# ddr3.net
KiCad netlist of a schematic drawn in Altium Designer
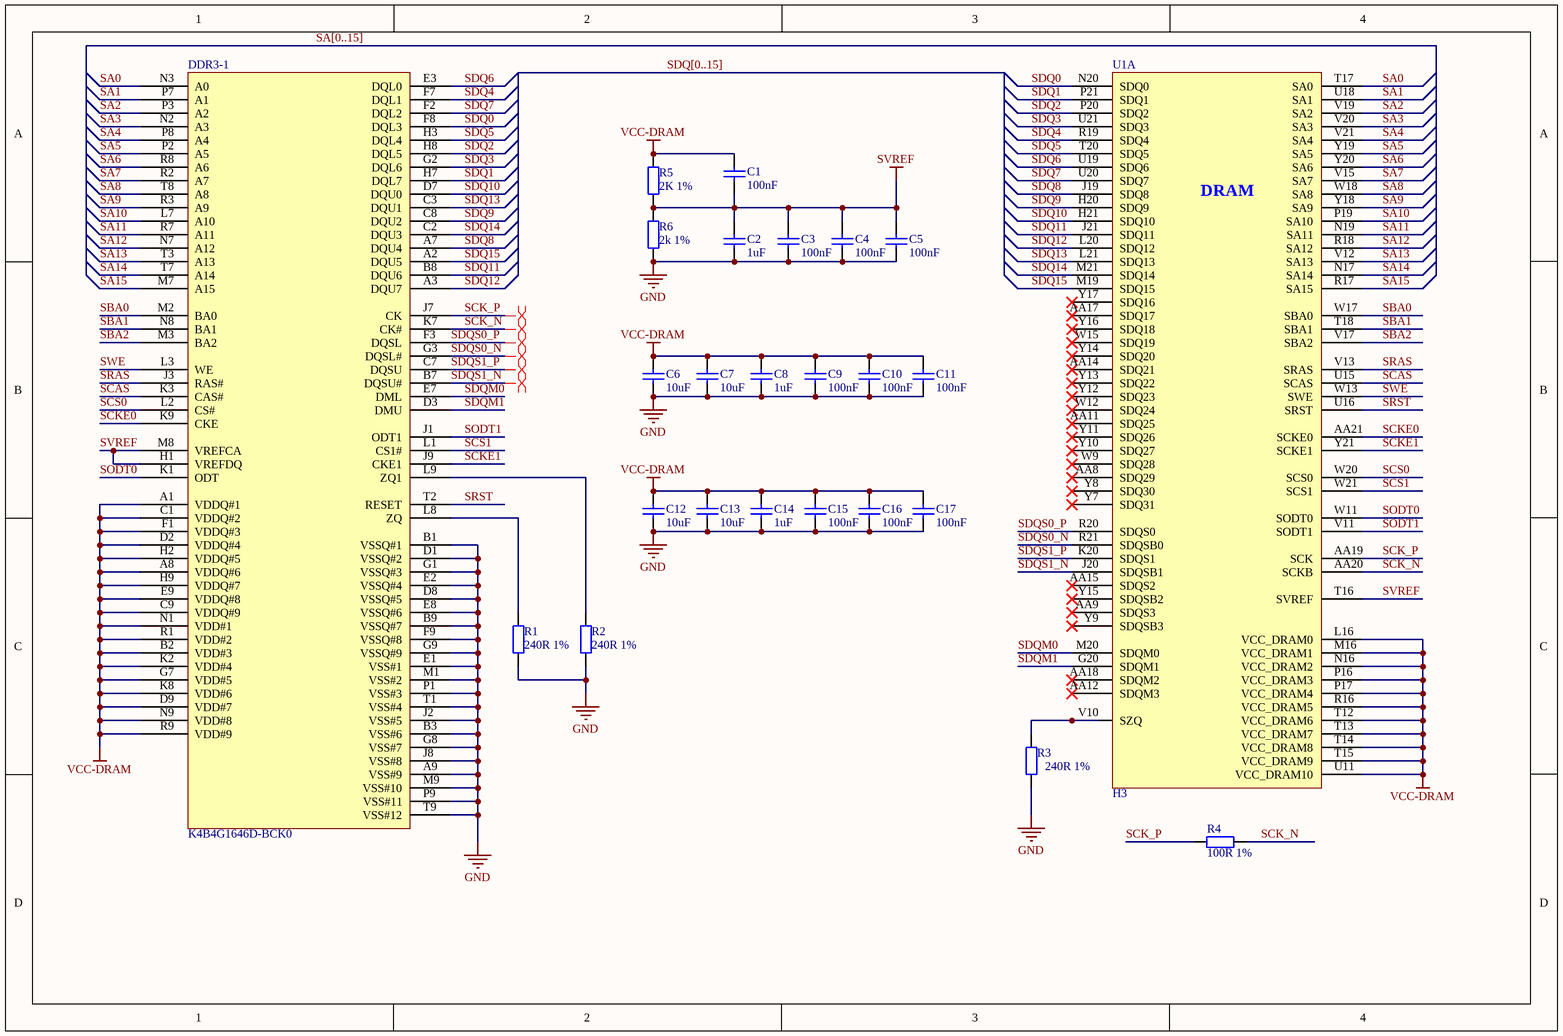
[diagram p0: ddr3.SchDoc]

(export (version "E")
  (design (tool "Eeschema 10.0.6"))
  (components
    (comp (ref "C1")
      (value "100nF")
      (footprint "0402_C")
      (description "smd capacitor")
      (libsource (lib "Schlib") (part "CAP-SMD"))
    )
    (comp (ref "C2")
      (value "1uF")
      (footprint "0402_C")
      (description "smd capacitor")
      (libsource (lib "Schlib") (part "CAP-SMD"))
    )
    (comp (ref "C3")
      (value "100nF")
      (footprint "0402_C")
      (description "smd capacitor")
      (libsource (lib "Schlib") (part "CAP-SMD"))
    )
    (comp (ref "C4")
      (value "100nF")
      (footprint "0402_C")
      (description "smd capacitor")
      (libsource (lib "Schlib") (part "CAP-SMD"))
    )
    (comp (ref "C5")
      (value "100nF")
      (footprint "0402_C")
      (description "smd capacitor")
      (libsource (lib "Schlib") (part "CAP-SMD"))
    )
    (comp (ref "C6")
      (value "10uF")
      (footprint "0402_C")
      (description "smd capacitor")
      (libsource (lib "Schlib") (part "CAP-SMD"))
    )
    (comp (ref "C7")
      (value "10uF")
      (footprint "0402_C")
      (description "smd capacitor")
      (libsource (lib "Schlib") (part "CAP-SMD"))
    )
    (comp (ref "C8")
      (value "1uF")
      (footprint "0402_C")
      (description "smd capacitor")
      (libsource (lib "Schlib") (part "CAP-SMD"))
    )
    (comp (ref "C9")
      (value "100nF")
      (footprint "0402_C")
      (description "smd capacitor")
      (libsource (lib "Schlib") (part "CAP-SMD"))
    )
    (comp (ref "C10")
      (value "100nF")
      (footprint "0402_C")
      (description "smd capacitor")
      (libsource (lib "Schlib") (part "CAP-SMD"))
    )
    (comp (ref "C11")
      (value "100nF")
      (footprint "0402_C")
      (description "smd capacitor")
      (libsource (lib "Schlib") (part "CAP-SMD"))
    )
    (comp (ref "C12")
      (value "10uF")
      (footprint "0402_C")
      (description "smd capacitor")
      (libsource (lib "Schlib") (part "CAP-SMD"))
    )
    (comp (ref "C13")
      (value "10uF")
      (footprint "0402_C")
      (description "smd capacitor")
      (libsource (lib "Schlib") (part "CAP-SMD"))
    )
    (comp (ref "C14")
      (value "1uF")
      (footprint "0402_C")
      (description "smd capacitor")
      (libsource (lib "Schlib") (part "CAP-SMD"))
    )
    (comp (ref "C15")
      (value "100nF")
      (footprint "0402_C")
      (description "smd capacitor")
      (libsource (lib "Schlib") (part "CAP-SMD"))
    )
    (comp (ref "C16")
      (value "100nF")
      (footprint "0402_C")
      (description "smd capacitor")
      (libsource (lib "Schlib") (part "CAP-SMD"))
    )
    (comp (ref "C17")
      (value "100nF")
      (footprint "0402_C")
      (description "smd capacitor")
      (libsource (lib "Schlib") (part "CAP-SMD"))
    )
    (comp (ref "DDR3-1")
      (value "K4B4G1646D-BCK0")
      (footprint "BGA96_DDR3")
      (description "ddr3 96 BGA")
      (libsource (lib "Schlib") (part "DDR3-96pin"))
    )
    (comp (ref "R1")
      (value "240R 1%")
      (footprint "0402_R")
      (description "smd resistor")
      (libsource (lib "") (part "RES-SMD_1"))
    )
    (comp (ref "R2")
      (value "240R 1%")
      (footprint "0402_R")
      (description "smd resistor")
      (libsource (lib "") (part "RES-SMD_1"))
    )
    (comp (ref "R3")
      (value "240R 1%")
      (footprint "0402_R")
      (description "smd resistor")
      (libsource (lib "") (part "RES-SMD_1"))
    )
    (comp (ref "R4")
      (value "100R 1%")
      (footprint "0402_R")
      (description "smd resistor")
      (libsource (lib "") (part "RES-SMD_2"))
    )
    (comp (ref "R5")
      (value "2K 1%")
      (footprint "0402_R")
      (description "smd resistor")
      (libsource (lib "") (part "RES-SMD_1"))
    )
    (comp (ref "R6")
      (value "2k 1%")
      (footprint "0402_R")
      (description "smd resistor")
      (libsource (lib "Schlib") (part "RES-SMD"))
    )
    (comp (ref "U1")
      (value "H3")
      (footprint "allwinner-h3")
      (description "CPU")
      (libsource (lib "Schlib") (part "H3_CPU"))
    )
  )
  (nets
    (net (code "1") (name "/SA0") (class "Default")
      (node (ref "DDR3-1") (pin "N3") (pinfunction "A0_N3") (pintype "passive"))
      (node (ref "U1") (pin "T17") (pinfunction "SA0_T17") (pintype "passive"))
    )
    (net (code "2") (name "/SA1") (class "Default")
      (node (ref "DDR3-1") (pin "P7") (pinfunction "A1_P7") (pintype "passive"))
      (node (ref "U1") (pin "U18") (pinfunction "SA1_U18") (pintype "passive"))
    )
    (net (code "3") (name "/SA2") (class "Default")
      (node (ref "DDR3-1") (pin "P3") (pinfunction "A2_P3") (pintype "passive"))
      (node (ref "U1") (pin "V19") (pinfunction "SA2_V19") (pintype "passive"))
    )
    (net (code "4") (name "/SA3") (class "Default")
      (node (ref "DDR3-1") (pin "N2") (pinfunction "A3_N2") (pintype "passive"))
      (node (ref "U1") (pin "V20") (pinfunction "SA3_V20") (pintype "passive"))
    )
    (net (code "5") (name "/SA4") (class "Default")
      (node (ref "DDR3-1") (pin "P8") (pinfunction "A4_P8") (pintype "passive"))
      (node (ref "U1") (pin "V21") (pinfunction "SA4_V21") (pintype "passive"))
    )
    (net (code "6") (name "/SA5") (class "Default")
      (node (ref "DDR3-1") (pin "P2") (pinfunction "A5_P2") (pintype "passive"))
      (node (ref "U1") (pin "Y19") (pinfunction "SA5_Y19") (pintype "passive"))
    )
    (net (code "7") (name "/SA6") (class "Default")
      (node (ref "DDR3-1") (pin "R8") (pinfunction "A6_R8") (pintype "passive"))
      (node (ref "U1") (pin "Y20") (pinfunction "SA6_Y20") (pintype "passive"))
    )
    (net (code "8") (name "/SA7") (class "Default")
      (node (ref "DDR3-1") (pin "R2") (pinfunction "A7_R2") (pintype "passive"))
      (node (ref "U1") (pin "V15") (pinfunction "SA7_V15") (pintype "passive"))
    )
    (net (code "9") (name "/SA8") (class "Default")
      (node (ref "DDR3-1") (pin "T8") (pinfunction "A8_T8") (pintype "passive"))
      (node (ref "U1") (pin "W18") (pinfunction "SA8_W18") (pintype "passive"))
    )
    (net (code "10") (name "/SA9") (class "Default")
      (node (ref "DDR3-1") (pin "R3") (pinfunction "A9_R3") (pintype "passive"))
      (node (ref "U1") (pin "Y18") (pinfunction "SA9_Y18") (pintype "passive"))
    )
    (net (code "11") (name "/SA10") (class "Default")
      (node (ref "DDR3-1") (pin "L7") (pinfunction "A10_L7") (pintype "passive"))
      (node (ref "U1") (pin "P19") (pinfunction "SA10_P19") (pintype "passive"))
    )
    (net (code "12") (name "/SA11") (class "Default")
      (node (ref "DDR3-1") (pin "R7") (pinfunction "A11_R7") (pintype "passive"))
      (node (ref "U1") (pin "N19") (pinfunction "SA11_N19") (pintype "passive"))
    )
    (net (code "13") (name "/SA12") (class "Default")
      (node (ref "DDR3-1") (pin "N7") (pinfunction "A12_N7") (pintype "passive"))
      (node (ref "U1") (pin "R18") (pinfunction "SA12_R18") (pintype "passive"))
    )
    (net (code "14") (name "/SA13") (class "Default")
      (node (ref "DDR3-1") (pin "T3") (pinfunction "A13_T3") (pintype "passive"))
      (node (ref "U1") (pin "V12") (pinfunction "SA13_V12") (pintype "passive"))
    )
    (net (code "15") (name "/SA14") (class "Default")
      (node (ref "DDR3-1") (pin "T7") (pinfunction "A14_T7") (pintype "passive"))
      (node (ref "U1") (pin "N17") (pinfunction "SA14_N17") (pintype "passive"))
    )
    (net (code "16") (name "/SA15") (class "Default")
      (node (ref "DDR3-1") (pin "M7") (pinfunction "A15_M7") (pintype "passive"))
      (node (ref "U1") (pin "R17") (pinfunction "SA15_R17") (pintype "passive"))
    )
    (net (code "18") (name "/SBA0") (class "Default")
      (node (ref "DDR3-1") (pin "M2") (pinfunction "BA0_M2") (pintype "passive"))
      (node (ref "U1") (pin "W17") (pinfunction "SBA0_W17") (pintype "passive"))
    )
    (net (code "19") (name "/SBA1") (class "Default")
      (node (ref "DDR3-1") (pin "N8") (pinfunction "BA1_N8") (pintype "passive"))
      (node (ref "U1") (pin "T18") (pinfunction "SBA1_T18") (pintype "passive"))
    )
    (net (code "20") (name "/SBA2") (class "Default")
      (node (ref "DDR3-1") (pin "M3") (pinfunction "BA2_M3") (pintype "passive"))
      (node (ref "U1") (pin "V17") (pinfunction "SBA2_V17") (pintype "passive"))
    )
    (net (code "21") (name "/SCAS") (class "Default")
      (node (ref "DDR3-1") (pin "K3") (pinfunction "CAS#_K3") (pintype "passive"))
      (node (ref "U1") (pin "U15") (pinfunction "SCAS_U15") (pintype "passive"))
    )
    (net (code "22") (name "/SCKE0") (class "Default")
      (node (ref "DDR3-1") (pin "K9") (pinfunction "CKE_K9") (pintype "passive"))
      (node (ref "U1") (pin "AA21") (pinfunction "SCKE0_AA21") (pintype "passive"))
    )
    (net (code "23") (name "/SCKE1") (class "Default")
      (node (ref "DDR3-1") (pin "J9") (pinfunction "CKE1_J9") (pintype "passive"))
      (node (ref "U1") (pin "Y21") (pinfunction "SCKE1_Y21") (pintype "passive"))
    )
    (net (code "24") (name "/SCK_N") (class "Default")
      (node (ref "DDR3-1") (pin "K7") (pinfunction "CK#_K7") (pintype "passive"))
      (node (ref "R4") (pin "2") (pinfunction "2_2") (pintype "passive"))
      (node (ref "U1") (pin "AA20") (pinfunction "SCKB_AA20") (pintype "passive"))
    )
    (net (code "25") (name "/SCK_P") (class "Default")
      (node (ref "DDR3-1") (pin "J7") (pinfunction "CK_J7") (pintype "passive"))
      (node (ref "R4") (pin "1") (pinfunction "1_1") (pintype "passive"))
      (node (ref "U1") (pin "AA19") (pinfunction "SCK_AA19") (pintype "passive"))
    )
    (net (code "26") (name "/SCS0") (class "Default")
      (node (ref "DDR3-1") (pin "L2") (pinfunction "CS#_L2") (pintype "passive"))
      (node (ref "U1") (pin "W20") (pinfunction "SCS0_W20") (pintype "passive"))
    )
    (net (code "27") (name "/SCS1") (class "Default")
      (node (ref "DDR3-1") (pin "L1") (pinfunction "CS1#_L1") (pintype "passive"))
      (node (ref "U1") (pin "W21") (pinfunction "SCS1_W21") (pintype "passive"))
    )
    (net (code "28") (name "/SDQ0") (class "Default")
      (node (ref "DDR3-1") (pin "F8") (pinfunction "DQL3_F8") (pintype "passive"))
      (node (ref "U1") (pin "N20") (pinfunction "SDQ0_N20") (pintype "passive"))
    )
    (net (code "29") (name "/SDQ1") (class "Default")
      (node (ref "DDR3-1") (pin "H7") (pinfunction "DQL7_H7") (pintype "passive"))
      (node (ref "U1") (pin "P21") (pinfunction "SDQ1_P21") (pintype "passive"))
    )
    (net (code "30") (name "/SDQ2") (class "Default")
      (node (ref "DDR3-1") (pin "H8") (pinfunction "DQL5_H8") (pintype "passive"))
      (node (ref "U1") (pin "P20") (pinfunction "SDQ2_P20") (pintype "passive"))
    )
    (net (code "31") (name "/SDQ3") (class "Default")
      (node (ref "DDR3-1") (pin "G2") (pinfunction "DQL6_G2") (pintype "passive"))
      (node (ref "U1") (pin "U21") (pinfunction "SDQ3_U21") (pintype "passive"))
    )
    (net (code "32") (name "/SDQ4") (class "Default")
      (node (ref "DDR3-1") (pin "F7") (pinfunction "DQL1_F7") (pintype "passive"))
      (node (ref "U1") (pin "R19") (pinfunction "SDQ4_R19") (pintype "passive"))
    )
    (net (code "33") (name "/SDQ5") (class "Default")
      (node (ref "DDR3-1") (pin "H3") (pinfunction "DQL4_H3") (pintype "passive"))
      (node (ref "U1") (pin "T20") (pinfunction "SDQ5_T20") (pintype "passive"))
    )
    (net (code "34") (name "/SDQ6") (class "Default")
      (node (ref "DDR3-1") (pin "E3") (pinfunction "DQL0_E3") (pintype "passive"))
      (node (ref "U1") (pin "U19") (pinfunction "SDQ6_U19") (pintype "passive"))
    )
    (net (code "35") (name "/SDQ7") (class "Default")
      (node (ref "DDR3-1") (pin "F2") (pinfunction "DQL2_F2") (pintype "passive"))
      (node (ref "U1") (pin "U20") (pinfunction "SDQ7_U20") (pintype "passive"))
    )
    (net (code "36") (name "/SDQ8") (class "Default")
      (node (ref "DDR3-1") (pin "A7") (pinfunction "DQU4_A7") (pintype "passive"))
      (node (ref "U1") (pin "J19") (pinfunction "SDQ8_J19") (pintype "passive"))
    )
    (net (code "37") (name "/SDQ9") (class "Default")
      (node (ref "DDR3-1") (pin "C8") (pinfunction "DQU2_C8") (pintype "passive"))
      (node (ref "U1") (pin "H20") (pinfunction "SDQ9_H20") (pintype "passive"))
    )
    (net (code "38") (name "/SDQ10") (class "Default")
      (node (ref "DDR3-1") (pin "D7") (pinfunction "DQU0_D7") (pintype "passive"))
      (node (ref "U1") (pin "H21") (pinfunction "SDQ10_H21") (pintype "passive"))
    )
    (net (code "39") (name "/SDQ11") (class "Default")
      (node (ref "DDR3-1") (pin "B8") (pinfunction "DQU6_B8") (pintype "passive"))
      (node (ref "U1") (pin "J21") (pinfunction "SDQ11_J21") (pintype "passive"))
    )
    (net (code "40") (name "/SDQ12") (class "Default")
      (node (ref "DDR3-1") (pin "A3") (pinfunction "DQU7_A3") (pintype "passive"))
      (node (ref "U1") (pin "L20") (pinfunction "SDQ12_L20") (pintype "passive"))
    )
    (net (code "41") (name "/SDQ13") (class "Default")
      (node (ref "DDR3-1") (pin "C3") (pinfunction "DQU1_C3") (pintype "passive"))
      (node (ref "U1") (pin "L21") (pinfunction "SDQ13_L21") (pintype "passive"))
    )
    (net (code "42") (name "/SDQ14") (class "Default")
      (node (ref "DDR3-1") (pin "C2") (pinfunction "DQU3_C2") (pintype "passive"))
      (node (ref "U1") (pin "M21") (pinfunction "SDQ14_M21") (pintype "passive"))
    )
    (net (code "43") (name "/SDQ15") (class "Default")
      (node (ref "DDR3-1") (pin "A2") (pinfunction "DQU5_A2") (pintype "passive"))
      (node (ref "U1") (pin "M19") (pinfunction "SDQ15_M19") (pintype "passive"))
    )
    (net (code "44") (name "/SDQM0") (class "Default")
      (node (ref "DDR3-1") (pin "E7") (pinfunction "DML_E7") (pintype "passive"))
      (node (ref "U1") (pin "M20") (pinfunction "SDQM0_M20") (pintype "passive"))
    )
    (net (code "45") (name "/SDQM1") (class "Default")
      (node (ref "DDR3-1") (pin "D3") (pinfunction "DMU_D3") (pintype "passive"))
      (node (ref "U1") (pin "G20") (pinfunction "SDQM1_G20") (pintype "passive"))
    )
    (net (code "46") (name "/SDQS0_N") (class "Default")
      (node (ref "DDR3-1") (pin "G3") (pinfunction "DQSL#_G3") (pintype "passive"))
      (node (ref "U1") (pin "R21") (pinfunction "SDQSB0_R21") (pintype "passive"))
    )
    (net (code "47") (name "/SDQS0_P") (class "Default")
      (node (ref "DDR3-1") (pin "F3") (pinfunction "DQSL_F3") (pintype "passive"))
      (node (ref "U1") (pin "R20") (pinfunction "SDQS0_R20") (pintype "passive"))
    )
    (net (code "48") (name "/SDQS1_N") (class "Default")
      (node (ref "DDR3-1") (pin "B7") (pinfunction "DQSU#_B7") (pintype "passive"))
      (node (ref "U1") (pin "J20") (pinfunction "SDQSB1_J20") (pintype "passive"))
    )
    (net (code "49") (name "/SDQS1_P") (class "Default")
      (node (ref "DDR3-1") (pin "C7") (pinfunction "DQSU_C7") (pintype "passive"))
      (node (ref "U1") (pin "K20") (pinfunction "SDQS1_K20") (pintype "passive"))
    )
    (net (code "51") (name "/SODT0") (class "Default")
      (node (ref "DDR3-1") (pin "K1") (pinfunction "ODT_K1") (pintype "passive"))
      (node (ref "U1") (pin "W11") (pinfunction "SODT0_W11") (pintype "passive"))
    )
    (net (code "52") (name "/SODT1") (class "Default")
      (node (ref "DDR3-1") (pin "J1") (pinfunction "ODT1_J1") (pintype "passive"))
      (node (ref "U1") (pin "V11") (pinfunction "SODT1_V11") (pintype "passive"))
    )
    (net (code "53") (name "/SRAS") (class "Default")
      (node (ref "DDR3-1") (pin "J3") (pinfunction "RAS#_J3") (pintype "passive"))
      (node (ref "U1") (pin "V13") (pinfunction "SRAS_V13") (pintype "passive"))
    )
    (net (code "54") (name "/SRST") (class "Default")
      (node (ref "DDR3-1") (pin "T2") (pinfunction "RESET_T2") (pintype "passive"))
      (node (ref "U1") (pin "U16") (pinfunction "SRST_U16") (pintype "passive"))
    )
    (net (code "55") (name "/SWE") (class "Default")
      (node (ref "DDR3-1") (pin "L3") (pinfunction "WE_L3") (pintype "passive"))
      (node (ref "U1") (pin "W13") (pinfunction "SWE_W13") (pintype "passive"))
    )
    (net (code "56") (name "GND") (class "Default")
      (node (ref "C10") (pin "2") (pintype "passive"))
      (node (ref "C11") (pin "2") (pintype "passive"))
      (node (ref "C12") (pin "2") (pintype "passive"))
      (node (ref "C13") (pin "2") (pintype "passive"))
      (node (ref "C14") (pin "2") (pintype "passive"))
      (node (ref "C15") (pin "2") (pintype "passive"))
      (node (ref "C16") (pin "2") (pintype "passive"))
      (node (ref "C17") (pin "2") (pintype "passive"))
      (node (ref "C2") (pin "2") (pintype "passive"))
      (node (ref "C3") (pin "2") (pintype "passive"))
      (node (ref "C4") (pin "2") (pintype "passive"))
      (node (ref "C5") (pin "2") (pintype "passive"))
      (node (ref "C6") (pin "2") (pintype "passive"))
      (node (ref "C7") (pin "2") (pintype "passive"))
      (node (ref "C8") (pin "2") (pintype "passive"))
      (node (ref "C9") (pin "2") (pintype "passive"))
      (node (ref "DDR3-1") (pin "A9") (pinfunction "VSS#9_A9") (pintype "passive"))
      (node (ref "DDR3-1") (pin "B1") (pinfunction "VSSQ#1_B1") (pintype "passive"))
      (node (ref "DDR3-1") (pin "B3") (pinfunction "VSS#6_B3") (pintype "passive"))
      (node (ref "DDR3-1") (pin "B9") (pinfunction "VSSQ#7_B9") (pintype "passive"))
      (node (ref "DDR3-1") (pin "D1") (pinfunction "VSSQ#2_D1") (pintype "passive"))
      (node (ref "DDR3-1") (pin "D8") (pinfunction "VSSQ#5_D8") (pintype "passive"))
      (node (ref "DDR3-1") (pin "E1") (pinfunction "VSS#1_E1") (pintype "passive"))
      (node (ref "DDR3-1") (pin "E2") (pinfunction "VSSQ#4_E2") (pintype "passive"))
      (node (ref "DDR3-1") (pin "E8") (pinfunction "VSSQ#6_E8") (pintype "passive"))
      (node (ref "DDR3-1") (pin "F9") (pinfunction "VSSQ#8_F9") (pintype "passive"))
      (node (ref "DDR3-1") (pin "G1") (pinfunction "VSSQ#3_G1") (pintype "passive"))
      (node (ref "DDR3-1") (pin "G8") (pinfunction "VSS#7_G8") (pintype "passive"))
      (node (ref "DDR3-1") (pin "G9") (pinfunction "VSSQ#9_G9") (pintype "passive"))
      (node (ref "DDR3-1") (pin "J2") (pinfunction "VSS#5_J2") (pintype "passive"))
      (node (ref "DDR3-1") (pin "J8") (pinfunction "VSS#8_J8") (pintype "passive"))
      (node (ref "DDR3-1") (pin "M1") (pinfunction "VSS#2_M1") (pintype "passive"))
      (node (ref "DDR3-1") (pin "M9") (pinfunction "VSS#10_M9") (pintype "passive"))
      (node (ref "DDR3-1") (pin "P1") (pinfunction "VSS#3_P1") (pintype "passive"))
      (node (ref "DDR3-1") (pin "P9") (pinfunction "VSS#11_P9") (pintype "passive"))
      (node (ref "DDR3-1") (pin "T1") (pinfunction "VSS#4_T1") (pintype "passive"))
      (node (ref "DDR3-1") (pin "T9") (pinfunction "VSS#12_T9") (pintype "passive"))
      (node (ref "R1") (pin "1") (pinfunction "1_1") (pintype "passive"))
      (node (ref "R2") (pin "1") (pinfunction "1_1") (pintype "passive"))
      (node (ref "R3") (pin "1") (pinfunction "1_1") (pintype "passive"))
      (node (ref "R6") (pin "2") (pinfunction "2_2") (pintype "passive"))
    )
    (net (code "57") (name "Net-(DDR3-1-ZQ)") (class "Default")
      (node (ref "DDR3-1") (pin "L8") (pinfunction "ZQ_L8") (pintype "passive"))
      (node (ref "R1") (pin "2") (pinfunction "2_2") (pintype "passive"))
    )
    (net (code "58") (name "Net-(DDR3-1-ZQ1)") (class "Default")
      (node (ref "DDR3-1") (pin "L9") (pinfunction "ZQ1_L9") (pintype "passive"))
      (node (ref "R2") (pin "2") (pinfunction "2_2") (pintype "passive"))
    )
    (net (code "59") (name "Net-(U1A-SZQ)") (class "Default")
      (node (ref "R3") (pin "2") (pinfunction "2_2") (pintype "passive"))
      (node (ref "U1") (pin "V10") (pinfunction "SZQ_V10") (pintype "passive"))
    )
    (net (code "60") (name "SVREF") (class "Default")
      (node (ref "C1") (pin "2") (pintype "passive"))
      (node (ref "C2") (pin "1") (pintype "passive"))
      (node (ref "C3") (pin "1") (pintype "passive"))
      (node (ref "C4") (pin "1") (pintype "passive"))
      (node (ref "C5") (pin "1") (pintype "passive"))
      (node (ref "DDR3-1") (pin "H1") (pinfunction "VREFDQ_H1") (pintype "passive"))
      (node (ref "DDR3-1") (pin "M8") (pinfunction "VREFCA_M8") (pintype "passive"))
      (node (ref "R5") (pin "1") (pinfunction "1_1") (pintype "passive"))
      (node (ref "R6") (pin "1") (pinfunction "1_1") (pintype "passive"))
      (node (ref "U1") (pin "T16") (pinfunction "SVREF_T16") (pintype "passive"))
    )
    (net (code "61") (name "VCC-DRAM") (class "Default")
      (node (ref "C1") (pin "1") (pintype "passive"))
      (node (ref "C10") (pin "1") (pintype "passive"))
      (node (ref "C11") (pin "1") (pintype "passive"))
      (node (ref "C12") (pin "1") (pintype "passive"))
      (node (ref "C13") (pin "1") (pintype "passive"))
      (node (ref "C14") (pin "1") (pintype "passive"))
      (node (ref "C15") (pin "1") (pintype "passive"))
      (node (ref "C16") (pin "1") (pintype "passive"))
      (node (ref "C17") (pin "1") (pintype "passive"))
      (node (ref "C6") (pin "1") (pintype "passive"))
      (node (ref "C7") (pin "1") (pintype "passive"))
      (node (ref "C8") (pin "1") (pintype "passive"))
      (node (ref "C9") (pin "1") (pintype "passive"))
      (node (ref "DDR3-1") (pin "A1") (pinfunction "VDDQ#1_A1") (pintype "passive"))
      (node (ref "DDR3-1") (pin "A8") (pinfunction "VDDQ#6_A8") (pintype "passive"))
      (node (ref "DDR3-1") (pin "B2") (pinfunction "VDD#3_B2") (pintype "passive"))
      (node (ref "DDR3-1") (pin "C1") (pinfunction "VDDQ#2_C1") (pintype "passive"))
      (node (ref "DDR3-1") (pin "C9") (pinfunction "VDDQ#9_C9") (pintype "passive"))
      (node (ref "DDR3-1") (pin "D2") (pinfunction "VDDQ#4_D2") (pintype "passive"))
      (node (ref "DDR3-1") (pin "D9") (pinfunction "VDD#7_D9") (pintype "passive"))
      (node (ref "DDR3-1") (pin "E9") (pinfunction "VDDQ#8_E9") (pintype "passive"))
      (node (ref "DDR3-1") (pin "F1") (pinfunction "VDDQ#3_F1") (pintype "passive"))
      (node (ref "DDR3-1") (pin "G7") (pinfunction "VDD#5_G7") (pintype "passive"))
      (node (ref "DDR3-1") (pin "H2") (pinfunction "VDDQ#5_H2") (pintype "passive"))
      (node (ref "DDR3-1") (pin "H9") (pinfunction "VDDQ#7_H9") (pintype "passive"))
      (node (ref "DDR3-1") (pin "K2") (pinfunction "VDD#4_K2") (pintype "passive"))
      (node (ref "DDR3-1") (pin "K8") (pinfunction "VDD#6_K8") (pintype "passive"))
      (node (ref "DDR3-1") (pin "N1") (pinfunction "VDD#1_N1") (pintype "passive"))
      (node (ref "DDR3-1") (pin "N9") (pinfunction "VDD#8_N9") (pintype "passive"))
      (node (ref "DDR3-1") (pin "R1") (pinfunction "VDD#2_R1") (pintype "passive"))
      (node (ref "DDR3-1") (pin "R9") (pinfunction "VDD#9_R9") (pintype "passive"))
      (node (ref "R5") (pin "2") (pinfunction "2_2") (pintype "passive"))
      (node (ref "U1") (pin "L16") (pinfunction "VCC_DRAM0_L16") (pintype "passive"))
      (node (ref "U1") (pin "M16") (pinfunction "VCC_DRAM1_M16") (pintype "passive"))
      (node (ref "U1") (pin "N16") (pinfunction "VCC_DRAM2_N16") (pintype "passive"))
      (node (ref "U1") (pin "P16") (pinfunction "VCC_DRAM3_P16") (pintype "passive"))
      (node (ref "U1") (pin "P17") (pinfunction "VCC_DRAM4_P17") (pintype "passive"))
      (node (ref "U1") (pin "R16") (pinfunction "VCC_DRAM5_R16") (pintype "passive"))
      (node (ref "U1") (pin "T12") (pinfunction "VCC_DRAM6_T12") (pintype "passive"))
      (node (ref "U1") (pin "T13") (pinfunction "VCC_DRAM7_T13") (pintype "passive"))
      (node (ref "U1") (pin "T14") (pinfunction "VCC_DRAM8_T14") (pintype "passive"))
      (node (ref "U1") (pin "T15") (pinfunction "VCC_DRAM9_T15") (pintype "passive"))
      (node (ref "U1") (pin "U11") (pinfunction "VCC_DRAM10_U11") (pintype "passive"))
    )
    (net (code "62") (name "unconnected-(U1A-SDQ16-PadY17)") (class "Default")
      (node (ref "U1") (pin "Y17") (pinfunction "SDQ16_Y17") (pintype "passive+no_connect"))
    )
    (net (code "63") (name "unconnected-(U1A-SDQ17-PadAA17)") (class "Default")
      (node (ref "U1") (pin "AA17") (pinfunction "SDQ17_AA17") (pintype "passive+no_connect"))
    )
    (net (code "64") (name "unconnected-(U1A-SDQ18-PadY16)") (class "Default")
      (node (ref "U1") (pin "Y16") (pinfunction "SDQ18_Y16") (pintype "passive+no_connect"))
    )
    (net (code "65") (name "unconnected-(U1A-SDQ19-PadW15)") (class "Default")
      (node (ref "U1") (pin "W15") (pinfunction "SDQ19_W15") (pintype "passive+no_connect"))
    )
    (net (code "66") (name "unconnected-(U1A-SDQ20-PadY14)") (class "Default")
      (node (ref "U1") (pin "Y14") (pinfunction "SDQ20_Y14") (pintype "passive+no_connect"))
    )
    (net (code "67") (name "unconnected-(U1A-SDQ21-PadAA14)") (class "Default")
      (node (ref "U1") (pin "AA14") (pinfunction "SDQ21_AA14") (pintype "passive+no_connect"))
    )
    (net (code "68") (name "unconnected-(U1A-SDQ22-PadY13)") (class "Default")
      (node (ref "U1") (pin "Y13") (pinfunction "SDQ22_Y13") (pintype "passive+no_connect"))
    )
    (net (code "69") (name "unconnected-(U1A-SDQ23-PadY12)") (class "Default")
      (node (ref "U1") (pin "Y12") (pinfunction "SDQ23_Y12") (pintype "passive+no_connect"))
    )
    (net (code "70") (name "unconnected-(U1A-SDQ24-PadW12)") (class "Default")
      (node (ref "U1") (pin "W12") (pinfunction "SDQ24_W12") (pintype "passive+no_connect"))
    )
    (net (code "71") (name "unconnected-(U1A-SDQ25-PadAA11)") (class "Default")
      (node (ref "U1") (pin "AA11") (pinfunction "SDQ25_AA11") (pintype "passive+no_connect"))
    )
    (net (code "72") (name "unconnected-(U1A-SDQ26-PadY11)") (class "Default")
      (node (ref "U1") (pin "Y11") (pinfunction "SDQ26_Y11") (pintype "passive+no_connect"))
    )
    (net (code "73") (name "unconnected-(U1A-SDQ27-PadY10)") (class "Default")
      (node (ref "U1") (pin "Y10") (pinfunction "SDQ27_Y10") (pintype "passive+no_connect"))
    )
    (net (code "74") (name "unconnected-(U1A-SDQ28-PadW9)") (class "Default")
      (node (ref "U1") (pin "W9") (pinfunction "SDQ28_W9") (pintype "passive+no_connect"))
    )
    (net (code "75") (name "unconnected-(U1A-SDQ29-PadAA8)") (class "Default")
      (node (ref "U1") (pin "AA8") (pinfunction "SDQ29_AA8") (pintype "passive+no_connect"))
    )
    (net (code "76") (name "unconnected-(U1A-SDQ30-PadY8)") (class "Default")
      (node (ref "U1") (pin "Y8") (pinfunction "SDQ30_Y8") (pintype "passive+no_connect"))
    )
    (net (code "77") (name "unconnected-(U1A-SDQ31-PadY7)") (class "Default")
      (node (ref "U1") (pin "Y7") (pinfunction "SDQ31_Y7") (pintype "passive+no_connect"))
    )
    (net (code "78") (name "unconnected-(U1A-SDQM2-PadAA18)") (class "Default")
      (node (ref "U1") (pin "AA18") (pinfunction "SDQM2_AA18") (pintype "passive+no_connect"))
    )
    (net (code "79") (name "unconnected-(U1A-SDQM3-PadAA12)") (class "Default")
      (node (ref "U1") (pin "AA12") (pinfunction "SDQM3_AA12") (pintype "passive+no_connect"))
    )
    (net (code "80") (name "unconnected-(U1A-SDQS2-PadAA15)") (class "Default")
      (node (ref "U1") (pin "AA15") (pinfunction "SDQS2_AA15") (pintype "passive+no_connect"))
    )
    (net (code "81") (name "unconnected-(U1A-SDQS3-PadAA9)") (class "Default")
      (node (ref "U1") (pin "AA9") (pinfunction "SDQS3_AA9") (pintype "passive+no_connect"))
    )
    (net (code "82") (name "unconnected-(U1A-SDQSB2-PadY15)") (class "Default")
      (node (ref "U1") (pin "Y15") (pinfunction "SDQSB2_Y15") (pintype "passive+no_connect"))
    )
    (net (code "83") (name "unconnected-(U1A-SDQSB3-PadY9)") (class "Default")
      (node (ref "U1") (pin "Y9") (pinfunction "SDQSB3_Y9") (pintype "passive+no_connect"))
    )
  )
)
